# Display.net
KiCad netlist of a schematic drawn in Altium Designer
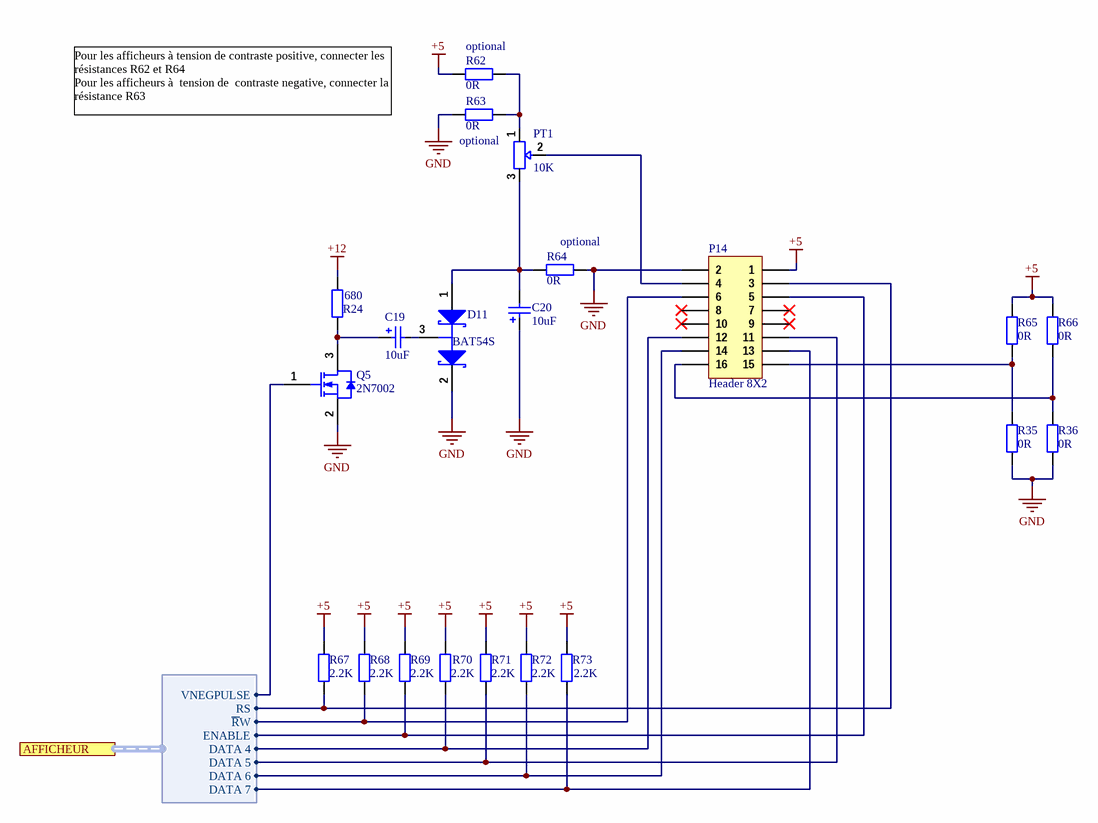
[diagram p0: Display.SchDoc]

(export (version "E")
  (design (tool "Eeschema 10.0.6"))
  (components
    (comp (ref "C19")
      (value "10uF")
      (footprint "SYLANN:KEMET_4")
      (description "Polarized Capacitor")
      (fields
        (field (name "MANUFACTURER") "KEMET")
        (field (name "MANUFACTURER PART NUMBER") "EXV106M025A9BAA")
      )
      (libsource (lib "BRA") (part "Cap Pol 10uF"))
    )
    (comp (ref "C20")
      (value "10uF")
      (footprint "SYLANN:KEMET_4")
      (description "Polarized Capacitor")
      (fields
        (field (name "MANUFACTURER") "KEMET")
        (field (name "MANUFACTURER PART NUMBER") "EXV106M025A9BAA")
      )
      (libsource (lib "BRA") (part "Cap Pol 10uF"))
    )
    (comp (ref "D11")
      (value "BAT54S")
      (footprint "SOT-23")
      (description "Schottky Barrier Double Diode")
      (fields (field (name "MANUFACTURER") "MULTICOMP") (field (name "PUBLISHER") "Altium Limited"))
      (libsource (lib "Philips Discrete Diode - Schottky") (part "BAT54S"))
    )
    (comp (ref "P14")
      (value "Header 8X2")
      (footprint "M20-2X8")
      (description "Header, 8-Pin, Dual row")
      (fields
        (field (name "MANUFACTURER") "HARWIN")
        (field (name "MANUFACTURER PART NUMBER") "M20-8760842")
        (field (name "PUBLISHER") "Altium Limited")
      )
      (libsource (lib "Miscellaneous Connectors") (part "Header 8X2"))
    )
    (comp (ref "PT1")
      (value "10K")
      (footprint "3361P")
      (fields
        (field (name "MANUFACTURER") "BOURNS")
        (field (name "MANUFACTURER PART NUMBER") "3361P-1-103GLF")
      )
      (libsource (lib "UTIL_Library") (part "RV"))
    )
    (comp (ref "Q5")
      (value "2N7002")
      (footprint "SOT23")
      (description "N-channel Enhancement Mode Field-effect Transistor")
      (fields (field (name "MANUFACTURER") "NXP") (field (name "PUBLISHER") "Altium Limited"))
      (libsource (lib "Philips Discrete MOSFET - Low Power") (part "2N7002"))
    )
    (comp (ref "R24")
      (value "680")
      (footprint "R0805")
      (description "Resistor")
      (libsource (lib "BRA") (part "Resistor 0805 680"))
    )
    (comp (ref "R35")
      (value "0R")
      (footprint "R0805")
      (description "Resistor or Jumper")
      (fields
        (field (name "MANUFACTURER") "MULTICOMP")
        (field (name "MANUFACTURER PART NUMBER") "MCMR08X000 PTL")
      )
      (libsource (lib "BRA") (part "Resistor 0805 0R"))
    )
    (comp (ref "R36")
      (value "0R")
      (footprint "R0805")
      (description "Resistor or Jumper")
      (fields
        (field (name "MANUFACTURER") "MULTICOMP")
        (field (name "MANUFACTURER PART NUMBER") "MCMR08X000 PTL")
      )
      (libsource (lib "BRA") (part "Resistor 0805 0R"))
    )
    (comp (ref "R62")
      (value "0R")
      (footprint "R0805")
      (description "Resistor or Jumper")
      (fields
        (field (name "MANUFACTURER") "MULTICOMP")
        (field (name "MANUFACTURER PART NUMBER") "MCMR08X000 PTL")
      )
      (libsource (lib "") (part "Resistor 0805 0R_1"))
    )
    (comp (ref "R63")
      (value "0R")
      (footprint "R0805")
      (description "Resistor or Jumper")
      (fields
        (field (name "MANUFACTURER") "MULTICOMP")
        (field (name "MANUFACTURER PART NUMBER") "MCMR08X000 PTL")
      )
      (libsource (lib "") (part "Resistor 0805 0R_1"))
    )
    (comp (ref "R64")
      (value "0R")
      (footprint "R0805")
      (description "Resistor or Jumper")
      (fields
        (field (name "MANUFACTURER") "MULTICOMP")
        (field (name "MANUFACTURER PART NUMBER") "MCMR08X000 PTL")
      )
      (libsource (lib "") (part "Resistor 0805 0R_1"))
    )
    (comp (ref "R65")
      (value "0R")
      (footprint "R0805")
      (description "Resistor or Jumper")
      (fields
        (field (name "MANUFACTURER") "MULTICOMP")
        (field (name "MANUFACTURER PART NUMBER") "MCMR08X000 PTL")
      )
      (libsource (lib "BRA") (part "Resistor 0805 0R"))
    )
    (comp (ref "R66")
      (value "0R")
      (footprint "R0805")
      (description "Resistor or Jumper")
      (fields
        (field (name "MANUFACTURER") "MULTICOMP")
        (field (name "MANUFACTURER PART NUMBER") "MCMR08X000 PTL")
      )
      (libsource (lib "BRA") (part "Resistor 0805 0R"))
    )
    (comp (ref "R67")
      (value "2.2K")
      (footprint "R0805")
      (description "Resistor")
      (fields
        (field (name "MANUFACTURER") "MULTICOMP")
        (field (name "MANUFACTURER PART NUMBER") "MC01W080512K2")
      )
      (libsource (lib "BRA") (part "Resistor 0805 2.2K"))
    )
    (comp (ref "R68")
      (value "2.2K")
      (footprint "R0805")
      (description "Resistor")
      (fields
        (field (name "MANUFACTURER") "MULTICOMP")
        (field (name "MANUFACTURER PART NUMBER") "MC01W080512K2")
      )
      (libsource (lib "BRA") (part "Resistor 0805 2.2K"))
    )
    (comp (ref "R69")
      (value "2.2K")
      (footprint "R0805")
      (description "Resistor")
      (fields
        (field (name "MANUFACTURER") "MULTICOMP")
        (field (name "MANUFACTURER PART NUMBER") "MC01W080512K2")
      )
      (libsource (lib "BRA") (part "Resistor 0805 2.2K"))
    )
    (comp (ref "R70")
      (value "2.2K")
      (footprint "R0805")
      (description "Resistor")
      (fields
        (field (name "MANUFACTURER") "MULTICOMP")
        (field (name "MANUFACTURER PART NUMBER") "MC01W080512K2")
      )
      (libsource (lib "BRA") (part "Resistor 0805 2.2K"))
    )
    (comp (ref "R71")
      (value "2.2K")
      (footprint "R0805")
      (description "Resistor")
      (fields
        (field (name "MANUFACTURER") "MULTICOMP")
        (field (name "MANUFACTURER PART NUMBER") "MC01W080512K2")
      )
      (libsource (lib "BRA") (part "Resistor 0805 2.2K"))
    )
    (comp (ref "R72")
      (value "2.2K")
      (footprint "R0805")
      (description "Resistor")
      (fields
        (field (name "MANUFACTURER") "MULTICOMP")
        (field (name "MANUFACTURER PART NUMBER") "MC01W080512K2")
      )
      (libsource (lib "BRA") (part "Resistor 0805 2.2K"))
    )
    (comp (ref "R73")
      (value "2.2K")
      (footprint "R0805")
      (description "Resistor")
      (fields
        (field (name "MANUFACTURER") "MULTICOMP")
        (field (name "MANUFACTURER PART NUMBER") "MC01W080512K2")
      )
      (libsource (lib "BRA") (part "Resistor 0805 2.2K"))
    )
  )
  (nets
    (net (code "3") (name "+5") (class "Default")
      (node (ref "P14") (pin "1") (pinfunction "1_1") (pintype "passive"))
      (node (ref "R62") (pin "2") (pinfunction "2_2") (pintype "passive"))
      (node (ref "R65") (pin "2") (pinfunction "2_2") (pintype "passive"))
      (node (ref "R66") (pin "2") (pinfunction "2_2") (pintype "passive"))
      (node (ref "R67") (pin "2") (pinfunction "2_2") (pintype "passive"))
      (node (ref "R68") (pin "2") (pinfunction "2_2") (pintype "passive"))
      (node (ref "R69") (pin "2") (pinfunction "2_2") (pintype "passive"))
      (node (ref "R70") (pin "2") (pinfunction "2_2") (pintype "passive"))
      (node (ref "R71") (pin "2") (pinfunction "2_2") (pintype "passive"))
      (node (ref "R72") (pin "2") (pinfunction "2_2") (pintype "passive"))
      (node (ref "R73") (pin "2") (pinfunction "2_2") (pintype "passive"))
    )
    (net (code "4") (name "+12") (class "Default")
      (node (ref "R24") (pin "2") (pinfunction "2_2") (pintype "passive"))
    )
    (net (code "5") (name "/DATA 4") (class "Default")
      (node (ref "P14") (pin "12") (pinfunction "12_12") (pintype "passive"))
      (node (ref "R70") (pin "1") (pinfunction "1_1") (pintype "passive"))
    )
    (net (code "6") (name "/DATA 5") (class "Default")
      (node (ref "P14") (pin "11") (pinfunction "11_11") (pintype "passive"))
      (node (ref "R71") (pin "1") (pinfunction "1_1") (pintype "passive"))
    )
    (net (code "7") (name "/DATA 6") (class "Default")
      (node (ref "P14") (pin "14") (pinfunction "14_14") (pintype "passive"))
      (node (ref "R72") (pin "1") (pinfunction "1_1") (pintype "passive"))
    )
    (net (code "8") (name "/DATA 7") (class "Default")
      (node (ref "P14") (pin "13") (pinfunction "13_13") (pintype "passive"))
      (node (ref "R73") (pin "1") (pinfunction "1_1") (pintype "passive"))
    )
    (net (code "9") (name "/ENABLE") (class "Default")
      (node (ref "P14") (pin "5") (pinfunction "5_5") (pintype "passive"))
      (node (ref "R69") (pin "1") (pinfunction "1_1") (pintype "passive"))
    )
    (net (code "10") (name "/RS") (class "Default")
      (node (ref "P14") (pin "3") (pinfunction "3_3") (pintype "passive"))
      (node (ref "R67") (pin "1") (pinfunction "1_1") (pintype "passive"))
    )
    (net (code "11") (name "/VNEGPULSE") (class "Default")
      (node (ref "Q5") (pin "1") (pinfunction "G_1") (pintype "passive"))
    )
    (net (code "13") (name "/~{R}W") (class "Default")
      (node (ref "P14") (pin "6") (pinfunction "6_6") (pintype "passive"))
      (node (ref "R68") (pin "1") (pinfunction "1_1") (pintype "passive"))
    )
    (net (code "14") (name "GND") (class "Default")
      (node (ref "C20") (pin "1") (pinfunction "1_1") (pintype "passive"))
      (node (ref "D11") (pin "2") (pinfunction "K_2") (pintype "passive"))
      (node (ref "P14") (pin "2") (pinfunction "2_2") (pintype "passive"))
      (node (ref "Q5") (pin "2") (pinfunction "S_2") (pintype "passive"))
      (node (ref "R35") (pin "1") (pinfunction "1_1") (pintype "passive"))
      (node (ref "R36") (pin "1") (pinfunction "1_1") (pintype "passive"))
      (node (ref "R63") (pin "2") (pinfunction "2_2") (pintype "passive"))
      (node (ref "R64") (pin "1") (pinfunction "1_1") (pintype "passive"))
    )
    (net (code "15") (name "Net-(D11-A)") (class "Default")
      (node (ref "C20") (pin "2") (pinfunction "2_2") (pintype "passive"))
      (node (ref "D11") (pin "1") (pinfunction "A_1") (pintype "passive"))
      (node (ref "PT1") (pin "3") (pinfunction "3_3") (pintype "passive"))
      (node (ref "R64") (pin "2") (pinfunction "2_2") (pintype "passive"))
    )
    (net (code "16") (name "Net-(D11-C)") (class "Default")
      (node (ref "C19") (pin "2") (pinfunction "2_2") (pintype "passive"))
      (node (ref "D11") (pin "3") (pinfunction "C_3") (pintype "passive"))
    )
    (net (code "17") (name "Net-(P14-Pad4)") (class "Default")
      (node (ref "P14") (pin "4") (pinfunction "4_4") (pintype "passive"))
      (node (ref "PT1") (pin "2") (pinfunction "2_2") (pintype "passive"))
    )
    (net (code "18") (name "Net-(P14-Pad15)") (class "Default")
      (node (ref "P14") (pin "15") (pinfunction "15_15") (pintype "passive"))
      (node (ref "R35") (pin "2") (pinfunction "2_2") (pintype "passive"))
      (node (ref "R65") (pin "1") (pinfunction "1_1") (pintype "passive"))
    )
    (net (code "19") (name "Net-(P14-Pad16)") (class "Default")
      (node (ref "P14") (pin "16") (pinfunction "16_16") (pintype "passive"))
      (node (ref "R36") (pin "2") (pinfunction "2_2") (pintype "passive"))
      (node (ref "R66") (pin "1") (pinfunction "1_1") (pintype "passive"))
    )
    (net (code "20") (name "Net-(PT1-Pad1)") (class "Default")
      (node (ref "PT1") (pin "1") (pinfunction "1_1") (pintype "passive"))
      (node (ref "R62") (pin "1") (pinfunction "1_1") (pintype "passive"))
      (node (ref "R63") (pin "1") (pinfunction "1_1") (pintype "passive"))
    )
    (net (code "21") (name "Net-(Q5-D)") (class "Default")
      (node (ref "C19") (pin "1") (pinfunction "1_1") (pintype "passive"))
      (node (ref "Q5") (pin "3") (pinfunction "D_3") (pintype "passive"))
      (node (ref "R24") (pin "1") (pinfunction "1_1") (pintype "passive"))
    )
    (net (code "22") (name "unconnected-(P14-Pad7)") (class "Default")
      (node (ref "P14") (pin "7") (pinfunction "7_7") (pintype "passive+no_connect"))
    )
    (net (code "23") (name "unconnected-(P14-Pad8)") (class "Default")
      (node (ref "P14") (pin "8") (pinfunction "8_8") (pintype "passive+no_connect"))
    )
    (net (code "24") (name "unconnected-(P14-Pad9)") (class "Default")
      (node (ref "P14") (pin "9") (pinfunction "9_9") (pintype "passive+no_connect"))
    )
    (net (code "25") (name "unconnected-(P14-Pad10)") (class "Default")
      (node (ref "P14") (pin "10") (pinfunction "10_10") (pintype "passive+no_connect"))
    )
  )
)
